# AC_POWER_Block.net
KiCad netlist of a schematic drawn in Altium Designer
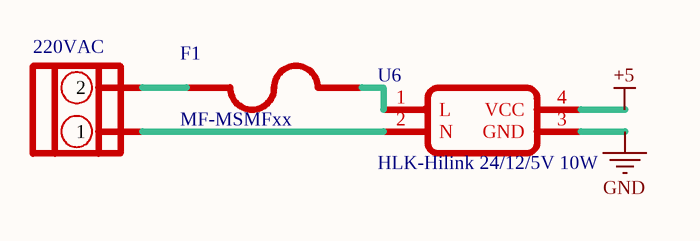
[diagram p0: AC_POWER_Block.SchDoc]

(export (version "E")
  (design (tool "Eeschema 10.0.6"))
  (components
    (comp (ref "F1")
      (value "MF-MSMFxx")
      (footprint "Fuse-1808")
      (description "MF-MSMF Series - PTC Resettable Fuses")
      (libsource (lib "CTAI-Library") (part "Fuse"))
    )
    (comp (ref "H2")
      (value "220VAC")
      (footprint "KF301-2-V")
      (description "Connector 5.08MM Pitch Vertical 2 Pole")
      (libsource (lib "CTAI-Library") (part "KF301-2-V"))
    )
    (comp (ref "U6")
      (value "HLK-Hilink 24/12/5V 10W")
      (footprint "HLK-HiLink AC-DC 10W")
      (description "Module AC to DC 220AC-24/12/5VDC 10W")
      (libsource (lib "CTAI-Library") (part "HLK-Hilink 24/12/5V 10W"))
    )
  )
  (nets
    (net (code "1") (name "+5") (class "Default")
      (node (ref "U6") (pin "4") (pinfunction "VCC_4") (pintype "power_in"))
    )
    (net (code "2") (name "GND") (class "Default")
      (node (ref "U6") (pin "3") (pinfunction "GND_3") (pintype "passive"))
    )
    (net (code "3") (name "Net-(F1-Pad1)") (class "Default")
      (node (ref "F1") (pin "1") (pinfunction "1_1") (pintype "passive"))
      (node (ref "H2") (pin "2") (pinfunction "2_2") (pintype "passive"))
    )
    (net (code "4") (name "Net-(U6-L)") (class "Default")
      (node (ref "F1") (pin "2") (pinfunction "2_2") (pintype "passive"))
      (node (ref "U6") (pin "1") (pinfunction "L_1") (pintype "output"))
    )
    (net (code "5") (name "Net-(U6-N)") (class "Default")
      (node (ref "H2") (pin "1") (pinfunction "1_1") (pintype "passive"))
      (node (ref "U6") (pin "2") (pinfunction "N_2") (pintype "passive"))
    )
  )
)
